# SPIFlash.net
KiCad netlist of a schematic drawn in Altium Designer
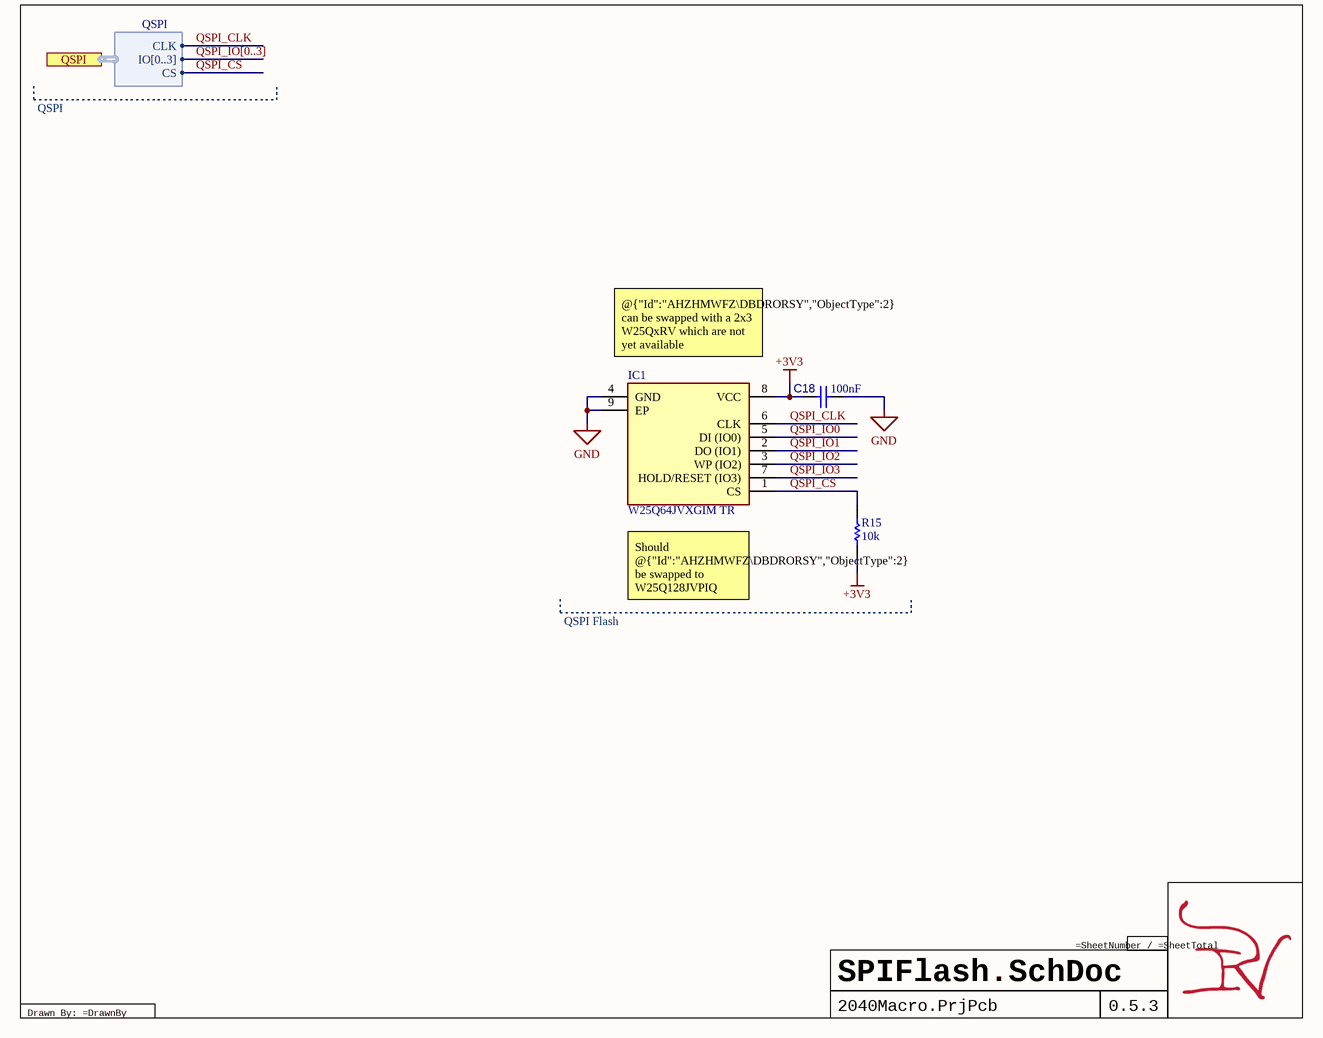
[diagram p0: SPIFlash.SchDoc]

(export (version "E")
  (design (tool "Eeschema 10.0.6"))
  (components
    (comp (ref "C18")
      (value "100nF")
      (footprint "CAP 0201_0603")
      (fields (field (name "Comment") "CL03A104KQ3NNNC"))
      (libsource (lib "IIT Motorsports") (part "CAP-NP-2"))
    )
    (comp (ref "IC1")
      (value "W25Q64JVXGIM TR")
      (footprint "SON80P400X400X50-9N")
      (description "NOR Flash Serial (SPI, Dual SPI, Quad SPI) 3V/3.3V 64M-bit 8M x 8 6ns 8-Pin XSON EP Tube")
      (fields (field (name "MOUSER PART NUMBER") "454-W25Q64JVXGIMTR"))
      (libsource (lib "IIT Motorsports") (part "W25Q64JVXGIM_TR"))
    )
    (comp (ref "R15")
      (value "10k")
      (footprint "RES 0201_0603")
      (fields
        (field (name "POWER") "50mW")
        (field (name "TOLERANCE") "1%")
        (field (name "Comment") "10k-0201-0.05/1")
      )
      (libsource (lib "IIT Motorsports") (part "RES"))
    )
  )
  (nets
    (net (code "2") (name "+3V3") (class "Default")
      (node (ref "C18") (pin "2") (pinfunction "2_2") (pintype "passive"))
      (node (ref "IC1") (pin "8") (pinfunction "VCC_8") (pintype "passive"))
      (node (ref "R15") (pin "1") (pinfunction "1_1") (pintype "passive"))
    )
    (net (code "3") (name "/QSPI_CLK") (class "Default")
      (node (ref "IC1") (pin "6") (pinfunction "CLK_6") (pintype "passive"))
    )
    (net (code "4") (name "/QSPI_CS") (class "Default")
      (node (ref "IC1") (pin "1") (pinfunction "CS_1") (pintype "passive"))
      (node (ref "R15") (pin "2") (pinfunction "2_2") (pintype "passive"))
    )
    (net (code "5") (name "/QSPI_IO0") (class "Default")
      (node (ref "IC1") (pin "5") (pinfunction "DI_(IO0)_5") (pintype "passive"))
    )
    (net (code "6") (name "/QSPI_IO1") (class "Default")
      (node (ref "IC1") (pin "2") (pinfunction "DO_(IO1)_2") (pintype "passive"))
    )
    (net (code "7") (name "/QSPI_IO2") (class "Default")
      (node (ref "IC1") (pin "3") (pinfunction "WP_(IO2)_3") (pintype "passive"))
    )
    (net (code "8") (name "/QSPI_IO3") (class "Default")
      (node (ref "IC1") (pin "7") (pinfunction "HOLD/RESET_(IO3)_7") (pintype "passive"))
    )
    (net (code "11") (name "GND") (class "Default")
      (node (ref "C18") (pin "1") (pinfunction "1_1") (pintype "passive"))
      (node (ref "IC1") (pin "4") (pinfunction "GND_4") (pintype "passive"))
      (node (ref "IC1") (pin "9") (pinfunction "EP_9") (pintype "passive"))
    )
  )
)
